# GPS_Module.net
KiCad netlist of a schematic drawn in EAGLE
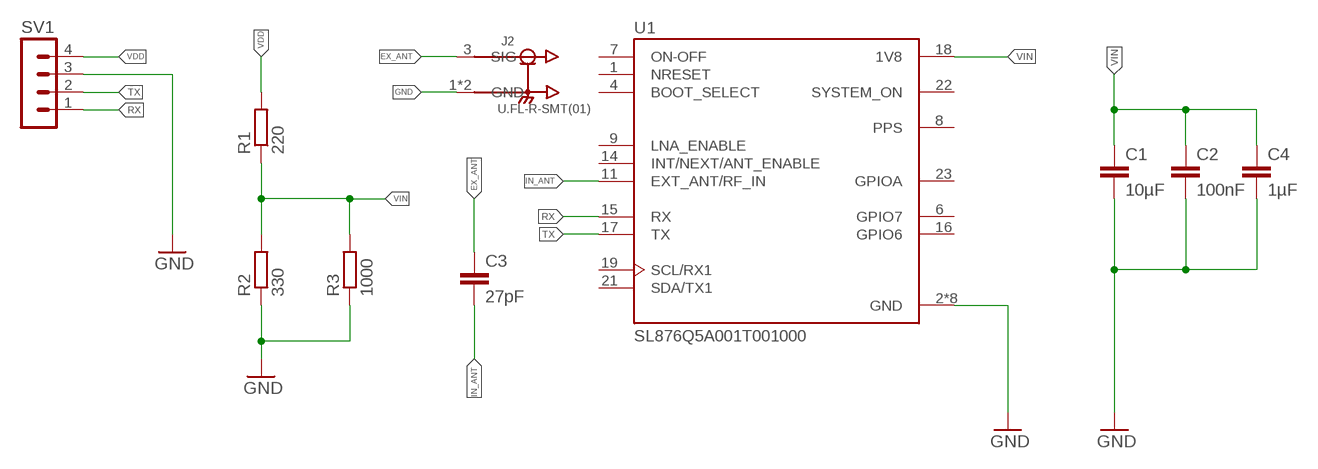
[diagram p0: schematic, sheet 1]

(export (version "E")
  (design (tool "Eeschema 10.0.6"))
  (components
    (comp (ref "C1")
      (value "10µF")
      (footprint "eagle-import:C0805")
      (libsource (lib "eagle-import") (part "C-EUC0805"))
    )
    (comp (ref "C2")
      (value "100nF")
      (footprint "eagle-import:C0805")
      (libsource (lib "eagle-import") (part "C-EUC0805"))
    )
    (comp (ref "C3")
      (value "27pF")
      (footprint "eagle-import:C0805")
      (libsource (lib "eagle-import") (part "C-EUC0805"))
    )
    (comp (ref "C4")
      (value "1µF")
      (footprint "eagle-import:C0805")
      (libsource (lib "eagle-import") (part "C-EUC0805"))
    )
    (comp (ref "J2")
      (value "U.FL-R-SMT(01)")
      (footprint "eagle-import:HRS_U.FL-R-SMT(01)")
      (fields (field (name "MF") "Hirose") (field (name "MP") "U.FL-R-SMT_01_"))
      (libsource (lib "eagle-import") (part "U.FL-R-SMT(01)"))
    )
    (comp (ref "R1")
      (value "220")
      (footprint "eagle-import:R0402")
      (libsource (lib "eagle-import") (part "R-EU_R0402"))
    )
    (comp (ref "R2")
      (value "330")
      (footprint "eagle-import:R0402")
      (libsource (lib "eagle-import") (part "R-EU_R0402"))
    )
    (comp (ref "R3")
      (value "1000")
      (footprint "eagle-import:R0402")
      (libsource (lib "eagle-import") (part "R-EU_R0402"))
    )
    (comp (ref "SV1")
      (value "MA04-1")
      (footprint "eagle-import:MA04-1")
      (libsource (lib "eagle-import") (part "MA04-1"))
    )
    (comp (ref "U1")
      (value "SL876Q5A001T001000")
      (footprint "eagle-import:XCVR_SL876Q5A001T001000")
      (fields (field (name "MF") "Telit"))
      (libsource (lib "eagle-import") (part "SL876Q5A001T001000"))
    )
  )
  (nets
    (net (code "1") (name "EX_ANT") (class "Default")
      (node (ref "C3") (pin "1") (pinfunction "1_1") (pintype "passive"))
      (node (ref "J2") (pin "3") (pinfunction "SIG_3") (pintype "passive"))
    )
    (net (code "2") (name "GND") (class "Default")
      (node (ref "C1") (pin "2") (pinfunction "2_2") (pintype "passive"))
      (node (ref "C2") (pin "2") (pinfunction "2_2") (pintype "passive"))
      (node (ref "C4") (pin "2") (pinfunction "2_2") (pintype "passive"))
      (node (ref "J2") (pin "1") (pinfunction "GND_1") (pintype "passive"))
      (node (ref "J2") (pin "2") (pinfunction "GND_2") (pintype "passive"))
      (node (ref "R2") (pin "1") (pinfunction "1_1") (pintype "passive"))
      (node (ref "R3") (pin "1") (pinfunction "1_1") (pintype "passive"))
      (node (ref "SV1") (pin "3") (pinfunction "3_3") (pintype "passive"))
      (node (ref "U1") (pin "10") (pinfunction "GND_10") (pintype "power_in"))
      (node (ref "U1") (pin "12") (pinfunction "GND_12") (pintype "power_in"))
      (node (ref "U1") (pin "13") (pinfunction "GND_13") (pintype "power_in"))
      (node (ref "U1") (pin "2") (pinfunction "GND_2") (pintype "power_in"))
      (node (ref "U1") (pin "20") (pinfunction "GND_20") (pintype "power_in"))
      (node (ref "U1") (pin "24") (pinfunction "GND_24") (pintype "power_in"))
      (node (ref "U1") (pin "3") (pinfunction "GND_3") (pintype "power_in"))
      (node (ref "U1") (pin "5") (pinfunction "GND_5") (pintype "power_in"))
    )
    (net (code "3") (name "IN_ANT") (class "Default")
      (node (ref "C3") (pin "2") (pinfunction "2_2") (pintype "passive"))
      (node (ref "U1") (pin "11") (pinfunction "EXT_ANT/RF_IN_11") (pintype "input"))
    )
    (net (code "4") (name "RX") (class "Default")
      (node (ref "SV1") (pin "1") (pinfunction "1_1") (pintype "passive"))
      (node (ref "U1") (pin "15") (pinfunction "RX_15") (pintype "input"))
    )
    (net (code "5") (name "TX") (class "Default")
      (node (ref "SV1") (pin "2") (pinfunction "2_2") (pintype "passive"))
      (node (ref "U1") (pin "17") (pinfunction "TX_17") (pintype "output"))
    )
    (net (code "6") (name "VDD") (class "Default")
      (node (ref "R1") (pin "2") (pinfunction "2_2") (pintype "passive"))
      (node (ref "SV1") (pin "4") (pinfunction "4_4") (pintype "passive"))
    )
    (net (code "7") (name "VIN") (class "Default")
      (node (ref "C1") (pin "1") (pinfunction "1_1") (pintype "passive"))
      (node (ref "C2") (pin "1") (pinfunction "1_1") (pintype "passive"))
      (node (ref "C4") (pin "1") (pinfunction "1_1") (pintype "passive"))
      (node (ref "R1") (pin "1") (pinfunction "1_1") (pintype "passive"))
      (node (ref "R2") (pin "2") (pinfunction "2_2") (pintype "passive"))
      (node (ref "R3") (pin "2") (pinfunction "2_2") (pintype "passive"))
      (node (ref "U1") (pin "18") (pinfunction "1V8_18") (pintype "power_in"))
    )
    (net (code "8") (name "unconnected-(U1-BOOT_SELECT-Pad4)") (class "Default")
      (node (ref "U1") (pin "4") (pinfunction "BOOT_SELECT_4") (pintype "input"))
    )
    (net (code "9") (name "unconnected-(U1-GPIO6-Pad16)") (class "Default")
      (node (ref "U1") (pin "16") (pinfunction "GPIO6_16") (pintype "bidirectional"))
    )
    (net (code "10") (name "unconnected-(U1-GPIO7-Pad6)") (class "Default")
      (node (ref "U1") (pin "6") (pinfunction "GPIO7_6") (pintype "bidirectional"))
    )
    (net (code "11") (name "unconnected-(U1-GPIOA-Pad23)") (class "Default")
      (node (ref "U1") (pin "23") (pinfunction "GPIOA_23") (pintype "output"))
    )
    (net (code "12") (name "unconnected-(U1-INT{slash}NEXT{slash}ANT_ENABLE-Pad14)") (class "Default")
      (node (ref "U1") (pin "14") (pinfunction "INT/NEXT/ANT_ENABLE_14") (pintype "input"))
    )
    (net (code "13") (name "unconnected-(U1-LNA_ENABLE-Pad9)") (class "Default")
      (node (ref "U1") (pin "9") (pinfunction "LNA_ENABLE_9") (pintype "output"))
    )
    (net (code "14") (name "unconnected-(U1-NRESET-Pad1)") (class "Default")
      (node (ref "U1") (pin "1") (pinfunction "NRESET_1") (pintype "input"))
    )
    (net (code "15") (name "unconnected-(U1-ON-OFF-Pad7)") (class "Default")
      (node (ref "U1") (pin "7") (pinfunction "ON-OFF_7") (pintype "input"))
    )
    (net (code "16") (name "unconnected-(U1-PPS-Pad8)") (class "Default")
      (node (ref "U1") (pin "8") (pinfunction "PPS_8") (pintype "output"))
    )
    (net (code "17") (name "unconnected-(U1-SCL{slash}RX1-Pad19)") (class "Default")
      (node (ref "U1") (pin "19") (pinfunction "SCL/RX1_19") (pintype "bidirectional"))
    )
    (net (code "18") (name "unconnected-(U1-SDA{slash}TX1-Pad21)") (class "Default")
      (node (ref "U1") (pin "21") (pinfunction "SDA/TX1_21") (pintype "bidirectional"))
    )
    (net (code "19") (name "unconnected-(U1-SYSTEM_ON-Pad22)") (class "Default")
      (node (ref "U1") (pin "22") (pinfunction "SYSTEM_ON_22") (pintype "output"))
    )
  )
)
